# Sensor_Board_0x09_0x10_Pulse_v1.net
KiCad netlist of a schematic drawn in EAGLE
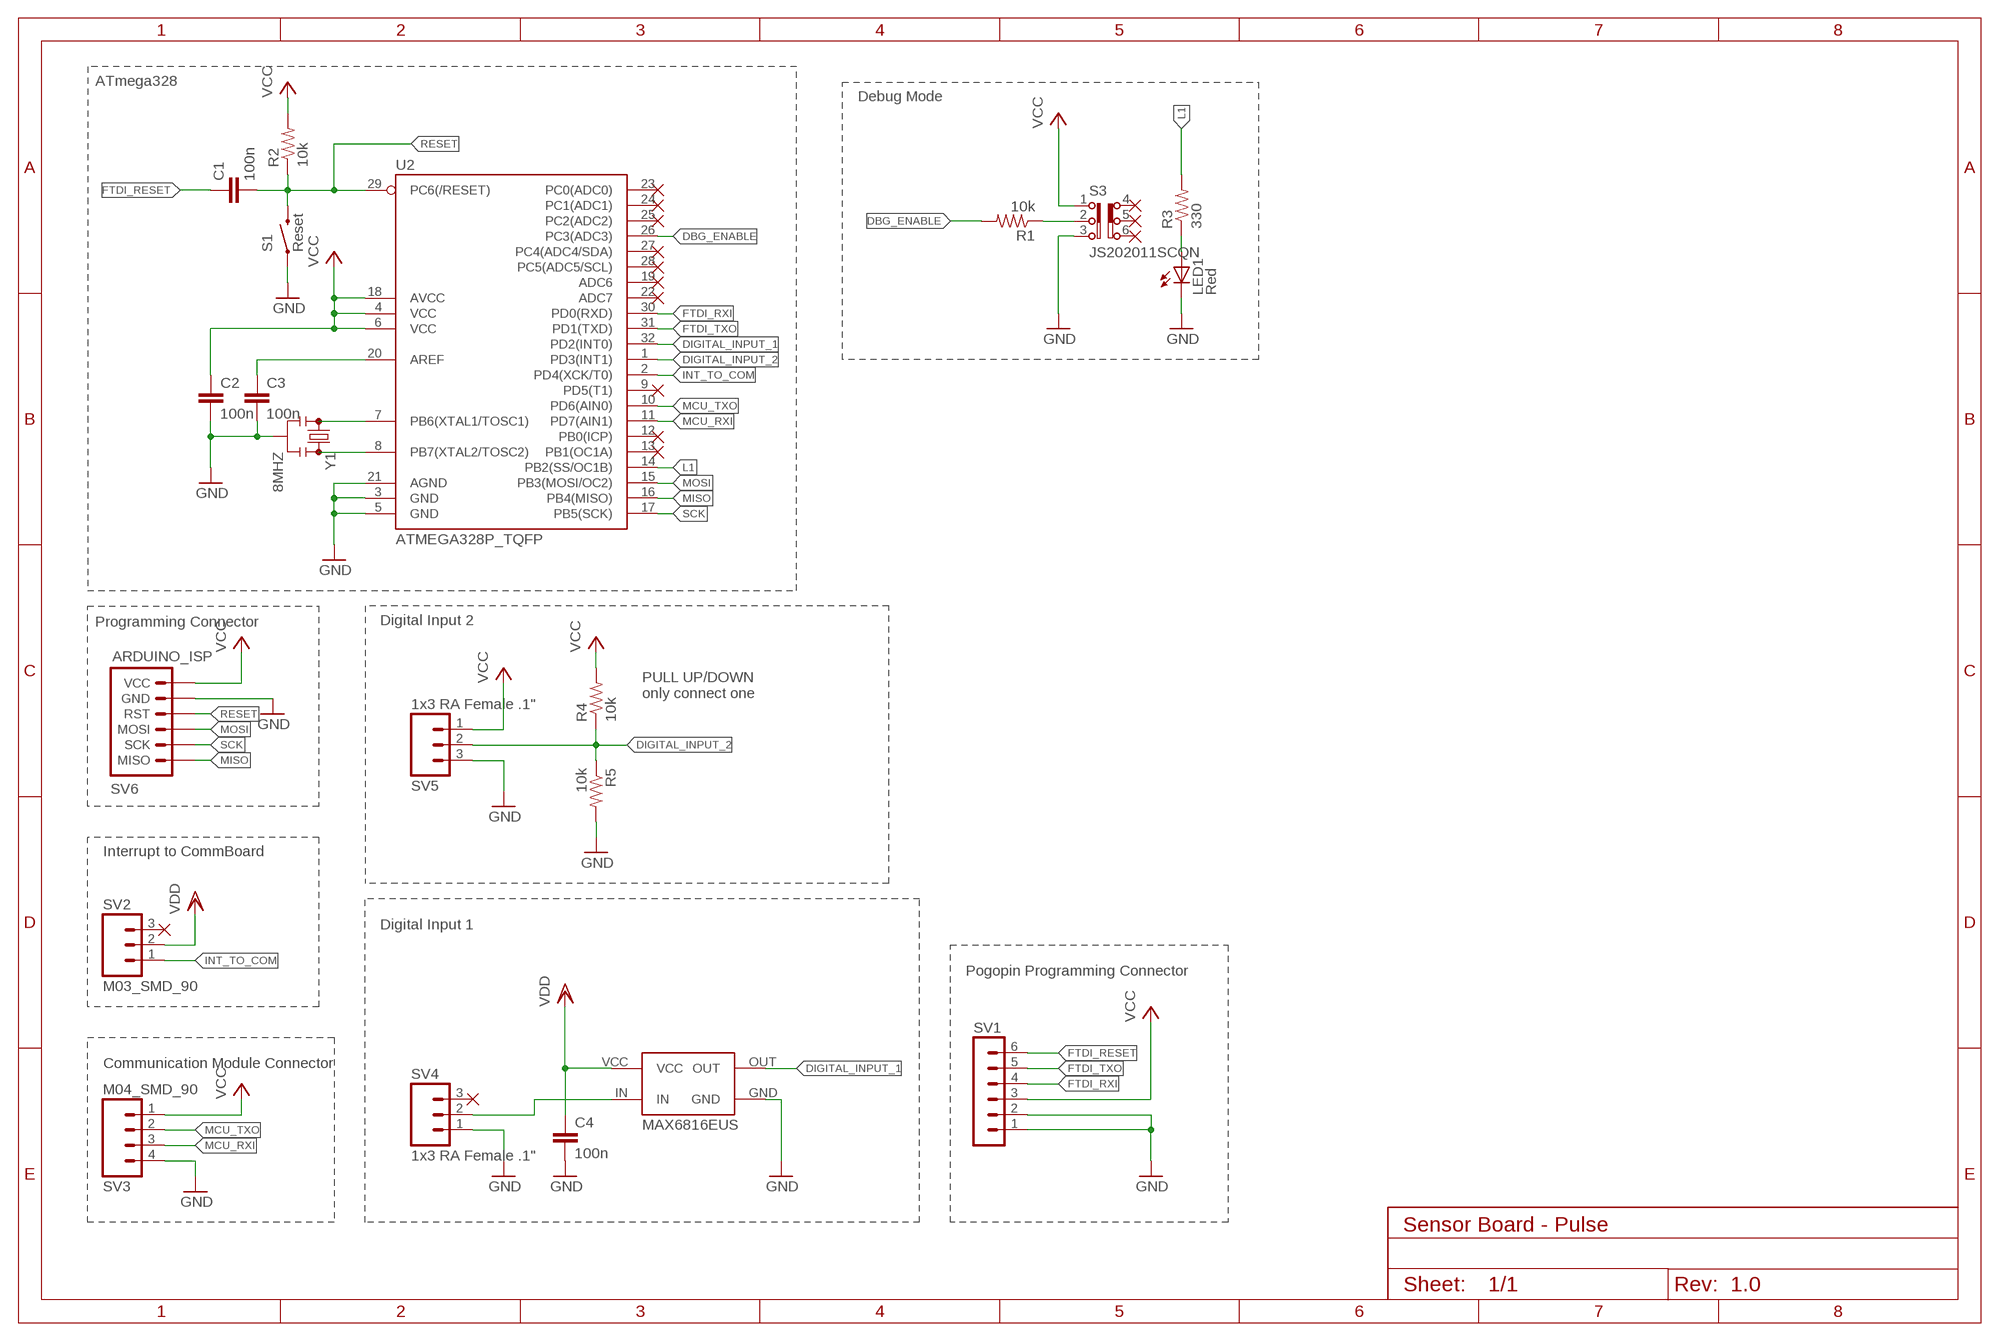
[diagram p0: schematic, sheet 1]

(export (version "E")
  (design (tool "Eeschema 10.0.6"))
  (components
    (comp (ref "C1")
      (value "100n")
      (footprint "eagle-import:C0805")
      (libsource (lib "eagle-import") (part "C"))
    )
    (comp (ref "C2")
      (value "100n")
      (footprint "eagle-import:C0805")
      (libsource (lib "eagle-import") (part "C"))
    )
    (comp (ref "C3")
      (value "100n")
      (footprint "eagle-import:C0805")
      (libsource (lib "eagle-import") (part "C"))
    )
    (comp (ref "C4")
      (value "100n")
      (footprint "eagle-import:C0805")
      (libsource (lib "eagle-import") (part "C"))
    )
    (comp (ref "LED1")
      (value "Red")
      (footprint "eagle-import:SML0805")
      (libsource (lib "eagle-import") (part "LEDSML0805"))
    )
    (comp (ref "R1")
      (value "10k")
      (footprint "eagle-import:0805")
      (libsource (lib "eagle-import") (part "RESISTOR0805-RES"))
    )
    (comp (ref "R2")
      (value "10k")
      (footprint "eagle-import:0805")
      (libsource (lib "eagle-import") (part "RESISTOR0805-RES"))
    )
    (comp (ref "R3")
      (value "330")
      (footprint "eagle-import:0805")
      (libsource (lib "eagle-import") (part "RESISTOR0805-RES"))
    )
    (comp (ref "R4")
      (value "10k")
      (footprint "eagle-import:0805")
      (libsource (lib "eagle-import") (part "RESISTOR0805-RES"))
    )
    (comp (ref "R5")
      (value "10k")
      (footprint "eagle-import:0805")
      (libsource (lib "eagle-import") (part "RESISTOR0805-RES"))
    )
    (comp (ref "S1")
      (value "Reset")
      (footprint "eagle-import:M-PUSHBUTTON-SMD")
      (libsource (lib "eagle-import") (part "PUSHBUTTON"))
    )
    (comp (ref "S3")
      (value "JS202011SCQN")
      (footprint "eagle-import:JS202011SCQN")
      (libsource (lib "eagle-import") (part "JS202011SCQN"))
    )
    (comp (ref "SV1")
      (value "MA06-1")
      (footprint "eagle-import:MA06-1")
      (libsource (lib "eagle-import") (part "MA06-1"))
    )
    (comp (ref "SV2")
      (value "M03_SMD_90")
      (footprint "eagle-import:M03_SMD_90")
      (libsource (lib "eagle-import") (part "M03_SMD_90"))
    )
    (comp (ref "SV3")
      (value "M04_SMD_90")
      (footprint "eagle-import:M04_SMD_90")
      (libsource (lib "eagle-import") (part "M04_SMD_90"))
    )
    (comp (ref "SV4")
      (value "1x3 RA Female .1\"")
      (footprint "eagle-import:1X03_SMD_RA_FEMALE")
      (libsource (lib "eagle-import") (part "M03SMD_RA_FEMALE"))
    )
    (comp (ref "SV5")
      (value "1x3 RA Female .1\"")
      (footprint "eagle-import:1X03_SMD_RA_FEMALE")
      (libsource (lib "eagle-import") (part "M03SMD_RA_FEMALE"))
    )
    (comp (ref "SV6")
      (value "ARDUINO_ISP")
      (footprint "eagle-import:M-2X3")
      (libsource (lib "eagle-import") (part "ARDUINO_ISP"))
    )
    (comp (ref "U$2")
      (value "MAX6816EUS")
      (footprint "eagle-import:SOT143")
      (libsource (lib "eagle-import") (part "MAX6816EUS"))
    )
    (comp (ref "U2")
      (value "ATMEGA328P_TQFP")
      (footprint "eagle-import:TQFP32-08")
      (libsource (lib "eagle-import") (part "ATMEGA328P_TQFP"))
    )
    (comp (ref "Y1")
      (value "8MHZ")
      (footprint "eagle-import:RESONATOR-SMD")
      (libsource (lib "eagle-import") (part "RESONATOR8MHZ"))
    )
  )
  (nets
    (net (code "1") (name "DBG_ENABLE") (class "Default")
      (node (ref "R1") (pin "2") (pinfunction "2_2") (pintype "passive"))
      (node (ref "U2") (pin "26") (pinfunction "PC3(ADC3)_26") (pintype "bidirectional"))
    )
    (net (code "2") (name "DIGITAL_INPUT_1") (class "Default")
      (node (ref "U$2") (pin "OUT") (pinfunction "OUT_OUT") (pintype "output"))
      (node (ref "U2") (pin "32") (pinfunction "PD2(INT0)_32") (pintype "bidirectional"))
    )
    (net (code "3") (name "DIGITAL_INPUT_2") (class "Default")
      (node (ref "R4") (pin "1") (pinfunction "1_1") (pintype "passive"))
      (node (ref "R5") (pin "1") (pinfunction "1_1") (pintype "passive"))
      (node (ref "SV5") (pin "2") (pinfunction "2_2") (pintype "passive"))
      (node (ref "U2") (pin "1") (pinfunction "PD3(INT1)_1") (pintype "bidirectional"))
    )
    (net (code "4") (name "FTDI_RESET") (class "Default")
      (node (ref "C1") (pin "1") (pinfunction "1_1") (pintype "passive"))
      (node (ref "SV1") (pin "6") (pinfunction "6_6") (pintype "passive"))
    )
    (net (code "5") (name "FTDI_RXI") (class "Default")
      (node (ref "SV1") (pin "4") (pinfunction "4_4") (pintype "passive"))
      (node (ref "U2") (pin "30") (pinfunction "PD0(RXD)_30") (pintype "bidirectional"))
    )
    (net (code "6") (name "FTDI_TXO") (class "Default")
      (node (ref "SV1") (pin "5") (pinfunction "5_5") (pintype "passive"))
      (node (ref "U2") (pin "31") (pinfunction "PD1(TXD)_31") (pintype "bidirectional"))
    )
    (net (code "7") (name "GND") (class "Default")
      (node (ref "C2") (pin "2") (pinfunction "2_2") (pintype "passive"))
      (node (ref "C3") (pin "2") (pinfunction "2_2") (pintype "passive"))
      (node (ref "C4") (pin "2") (pinfunction "2_2") (pintype "passive"))
      (node (ref "LED1") (pin "C") (pinfunction "C_C") (pintype "passive"))
      (node (ref "R5") (pin "2") (pinfunction "2_2") (pintype "passive"))
      (node (ref "S1") (pin "1") (pinfunction "LEFT_1") (pintype "passive"))
      (node (ref "S1") (pin "2") (pinfunction "LEFT_2") (pintype "passive"))
      (node (ref "S3") (pin "3") (pinfunction "3_3") (pintype "passive"))
      (node (ref "SV1") (pin "1") (pinfunction "1_1") (pintype "passive"))
      (node (ref "SV1") (pin "2") (pinfunction "2_2") (pintype "passive"))
      (node (ref "SV3") (pin "4") (pinfunction "4_4") (pintype "passive"))
      (node (ref "SV4") (pin "1") (pinfunction "1_1") (pintype "passive"))
      (node (ref "SV5") (pin "3") (pinfunction "3_3") (pintype "passive"))
      (node (ref "SV6") (pin "P$5") (pinfunction "GND_P$5") (pintype "passive"))
      (node (ref "U$2") (pin "GND") (pinfunction "GND_GND") (pintype "power_in"))
      (node (ref "U2") (pin "21") (pinfunction "AGND_21") (pintype "bidirectional"))
      (node (ref "U2") (pin "3") (pinfunction "GND_3") (pintype "bidirectional"))
      (node (ref "U2") (pin "5") (pinfunction "GND_5") (pintype "bidirectional"))
      (node (ref "Y1") (pin "2") (pinfunction "2_2") (pintype "passive"))
    )
    (net (code "8") (name "INT_TO_COM") (class "Default")
      (node (ref "SV2") (pin "1") (pinfunction "1_1") (pintype "passive"))
      (node (ref "U2") (pin "2") (pinfunction "PD4(XCK/T0)_2") (pintype "bidirectional"))
    )
    (net (code "9") (name "L1") (class "Default")
      (node (ref "R3") (pin "2") (pinfunction "2_2") (pintype "passive"))
      (node (ref "U2") (pin "14") (pinfunction "PB2(SS/OC1B)_14") (pintype "bidirectional"))
    )
    (net (code "10") (name "MCU_RXI") (class "Default")
      (node (ref "SV3") (pin "3") (pinfunction "3_3") (pintype "passive"))
      (node (ref "U2") (pin "11") (pinfunction "PD7(AIN1)_11") (pintype "bidirectional"))
    )
    (net (code "11") (name "MCU_TXO") (class "Default")
      (node (ref "SV3") (pin "2") (pinfunction "2_2") (pintype "passive"))
      (node (ref "U2") (pin "10") (pinfunction "PD6(AIN0)_10") (pintype "bidirectional"))
    )
    (net (code "12") (name "MISO") (class "Default")
      (node (ref "SV6") (pin "P$1") (pinfunction "MISO_P$1") (pintype "passive"))
      (node (ref "U2") (pin "16") (pinfunction "PB4(MISO)_16") (pintype "bidirectional"))
    )
    (net (code "13") (name "MOSI") (class "Default")
      (node (ref "SV6") (pin "P$3") (pinfunction "MOSI_P$3") (pintype "passive"))
      (node (ref "U2") (pin "15") (pinfunction "PB3(MOSI/OC2)_15") (pintype "bidirectional"))
    )
    (net (code "14") (name "Net-(LED1-PadA)") (class "Default")
      (node (ref "LED1") (pin "A") (pinfunction "A_A") (pintype "passive"))
      (node (ref "R3") (pin "1") (pinfunction "1_1") (pintype "passive"))
    )
    (net (code "15") (name "Net-(R1-Pad1)") (class "Default")
      (node (ref "R1") (pin "1") (pinfunction "1_1") (pintype "passive"))
      (node (ref "S3") (pin "2") (pinfunction "2_2") (pintype "passive"))
    )
    (net (code "16") (name "Net-(SV4-Pad2)") (class "Default")
      (node (ref "SV4") (pin "2") (pinfunction "2_2") (pintype "passive"))
      (node (ref "U$2") (pin "IN") (pinfunction "IN_IN") (pintype "input"))
    )
    (net (code "17") (name "Net-(U2-AREF)") (class "Default")
      (node (ref "C3") (pin "1") (pinfunction "1_1") (pintype "passive"))
      (node (ref "U2") (pin "20") (pinfunction "AREF_20") (pintype "bidirectional"))
    )
    (net (code "18") (name "Net-(U2-PB6(XTAL1{slash}TOSC1))") (class "Default")
      (node (ref "U2") (pin "7") (pinfunction "PB6(XTAL1/TOSC1)_7") (pintype "bidirectional"))
      (node (ref "Y1") (pin "1") (pinfunction "1_1") (pintype "passive"))
    )
    (net (code "19") (name "Net-(U2-PB7(XTAL2{slash}TOSC2))") (class "Default")
      (node (ref "U2") (pin "8") (pinfunction "PB7(XTAL2/TOSC2)_8") (pintype "bidirectional"))
      (node (ref "Y1") (pin "3") (pinfunction "3_3") (pintype "passive"))
    )
    (net (code "20") (name "RESET") (class "Default")
      (node (ref "C1") (pin "2") (pinfunction "2_2") (pintype "passive"))
      (node (ref "R2") (pin "1") (pinfunction "1_1") (pintype "passive"))
      (node (ref "S1") (pin "3") (pinfunction "RIGHT_3") (pintype "passive"))
      (node (ref "S1") (pin "4") (pinfunction "RIGHT_4") (pintype "passive"))
      (node (ref "SV6") (pin "P$4") (pinfunction "RST_P$4") (pintype "passive"))
      (node (ref "U2") (pin "29") (pinfunction "PC6(/RESET)_29") (pintype "bidirectional"))
    )
    (net (code "21") (name "SCK") (class "Default")
      (node (ref "SV6") (pin "P$2") (pinfunction "SCK_P$2") (pintype "passive"))
      (node (ref "U2") (pin "17") (pinfunction "PB5(SCK)_17") (pintype "bidirectional"))
    )
    (net (code "22") (name "VCC") (class "Default")
      (node (ref "C2") (pin "1") (pinfunction "1_1") (pintype "passive"))
      (node (ref "R2") (pin "2") (pinfunction "2_2") (pintype "passive"))
      (node (ref "R4") (pin "2") (pinfunction "2_2") (pintype "passive"))
      (node (ref "S3") (pin "1") (pinfunction "1_1") (pintype "passive"))
      (node (ref "SV1") (pin "3") (pinfunction "3_3") (pintype "passive"))
      (node (ref "SV3") (pin "1") (pinfunction "1_1") (pintype "passive"))
      (node (ref "SV5") (pin "1") (pinfunction "1_1") (pintype "passive"))
      (node (ref "SV6") (pin "P$6") (pinfunction "VCC_P$6") (pintype "passive"))
      (node (ref "U2") (pin "18") (pinfunction "AVCC_18") (pintype "bidirectional"))
      (node (ref "U2") (pin "4") (pinfunction "VCC_4") (pintype "bidirectional"))
      (node (ref "U2") (pin "6") (pinfunction "VCC_6") (pintype "bidirectional"))
    )
    (net (code "23") (name "VDD") (class "Default")
      (node (ref "C4") (pin "1") (pinfunction "1_1") (pintype "passive"))
      (node (ref "SV2") (pin "2") (pinfunction "2_2") (pintype "passive"))
      (node (ref "U$2") (pin "VCC") (pinfunction "VCC_VCC") (pintype "power_in"))
    )
    (net (code "24") (name "unconnected-(S3-Pad4)") (class "Default")
      (node (ref "S3") (pin "4") (pinfunction "4_4") (pintype "passive"))
    )
    (net (code "25") (name "unconnected-(S3-Pad5)") (class "Default")
      (node (ref "S3") (pin "5") (pinfunction "5_5") (pintype "passive"))
    )
    (net (code "26") (name "unconnected-(S3-Pad6)") (class "Default")
      (node (ref "S3") (pin "6") (pinfunction "6_6") (pintype "passive"))
    )
    (net (code "27") (name "unconnected-(SV2-Pad3)") (class "Default")
      (node (ref "SV2") (pin "3") (pinfunction "3_3") (pintype "passive"))
    )
    (net (code "28") (name "unconnected-(SV4-Pad3)") (class "Default")
      (node (ref "SV4") (pin "3") (pinfunction "3_3") (pintype "passive"))
    )
    (net (code "29") (name "unconnected-(U2-ADC6-Pad19)") (class "Default")
      (node (ref "U2") (pin "19") (pinfunction "ADC6_19") (pintype "bidirectional"))
    )
    (net (code "30") (name "unconnected-(U2-ADC7-Pad22)") (class "Default")
      (node (ref "U2") (pin "22") (pinfunction "ADC7_22") (pintype "bidirectional"))
    )
    (net (code "31") (name "unconnected-(U2-PB0(ICP)-Pad12)") (class "Default")
      (node (ref "U2") (pin "12") (pinfunction "PB0(ICP)_12") (pintype "bidirectional"))
    )
    (net (code "32") (name "unconnected-(U2-PB1(OC1A)-Pad13)") (class "Default")
      (node (ref "U2") (pin "13") (pinfunction "PB1(OC1A)_13") (pintype "bidirectional"))
    )
    (net (code "33") (name "unconnected-(U2-PC0(ADC0)-Pad23)") (class "Default")
      (node (ref "U2") (pin "23") (pinfunction "PC0(ADC0)_23") (pintype "bidirectional"))
    )
    (net (code "34") (name "unconnected-(U2-PC1(ADC1)-Pad24)") (class "Default")
      (node (ref "U2") (pin "24") (pinfunction "PC1(ADC1)_24") (pintype "bidirectional"))
    )
    (net (code "35") (name "unconnected-(U2-PC2(ADC2)-Pad25)") (class "Default")
      (node (ref "U2") (pin "25") (pinfunction "PC2(ADC2)_25") (pintype "bidirectional"))
    )
    (net (code "36") (name "unconnected-(U2-PC4(ADC4{slash}SDA)-Pad27)") (class "Default")
      (node (ref "U2") (pin "27") (pinfunction "PC4(ADC4/SDA)_27") (pintype "bidirectional"))
    )
    (net (code "37") (name "unconnected-(U2-PC5(ADC5{slash}SCL)-Pad28)") (class "Default")
      (node (ref "U2") (pin "28") (pinfunction "PC5(ADC5/SCL)_28") (pintype "bidirectional"))
    )
    (net (code "38") (name "unconnected-(U2-PD5(T1)-Pad9)") (class "Default")
      (node (ref "U2") (pin "9") (pinfunction "PD5(T1)_9") (pintype "bidirectional"))
    )
  )
)
